# BE2022L-V10.net
KiCad netlist of a schematic drawn in Altium Designer
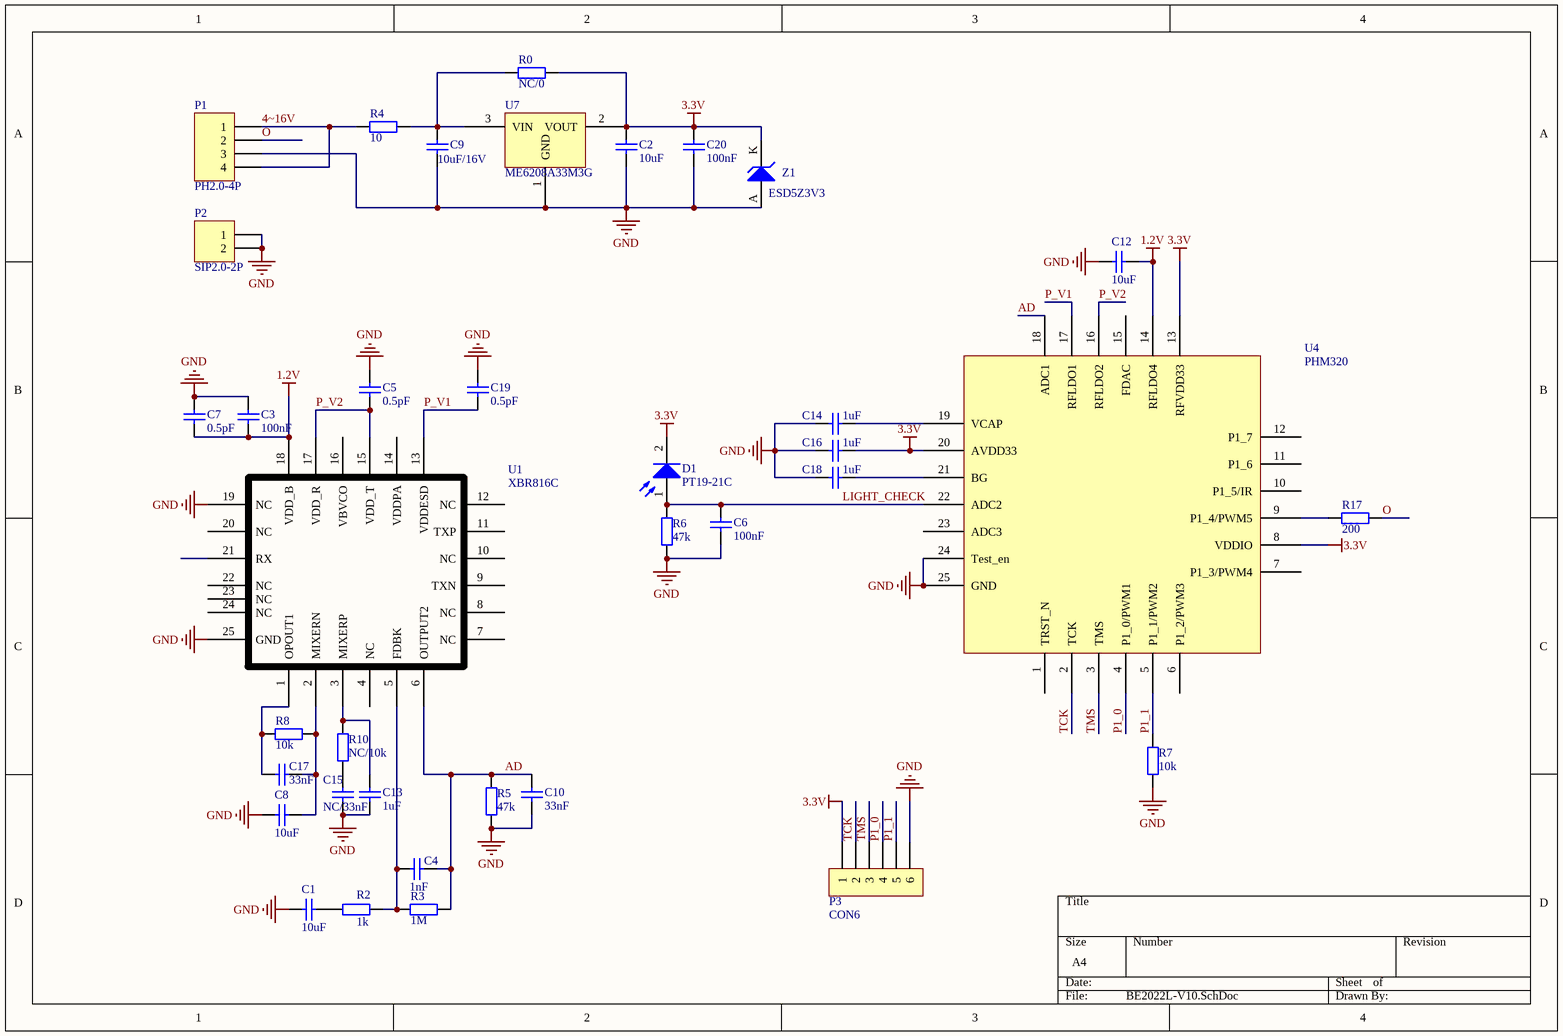
[diagram p0: BE2022L-V10.SchDoc]

(export (version "E")
  (design (tool "Eeschema 10.0.6"))
  (components
    (comp (ref "C1")
      (value "10uF")
      (footprint "C0402")
      (description "Capacitor")
      (fields (field (name "PUBLISHER") "Altium Limited"))
      (libsource (lib "") (part "Cap_1"))
    )
    (comp (ref "C2")
      (value "10uF")
      (footprint "C0402")
      (description "Capacitor")
      (fields (field (name "PUBLISHER") "Altium Limited"))
      (libsource (lib "") (part "Cap_1"))
    )
    (comp (ref "C3")
      (value "100nF")
      (footprint "C0402")
      (description "Capacitor")
      (fields (field (name "PUBLISHER") "Altium Limited"))
      (libsource (lib "") (part "Cap_1"))
    )
    (comp (ref "C4")
      (value "1nF")
      (footprint "C0402")
      (description "Capacitor")
      (fields (field (name "PUBLISHER") "Altium Limited"))
      (libsource (lib "") (part "Cap_1"))
    )
    (comp (ref "C5")
      (value "0.5pF")
      (footprint "C0402")
      (description "Capacitor")
      (fields (field (name "PUBLISHER") "Altium Limited"))
      (libsource (lib "") (part "Cap_1"))
    )
    (comp (ref "C6")
      (value "100nF")
      (footprint "C0402")
      (description "Capacitor")
      (fields (field (name "PUBLISHER") "Altium Limited"))
      (libsource (lib "") (part "Cap_1"))
    )
    (comp (ref "C7")
      (value "0.5pF")
      (footprint "C0402")
      (description "Capacitor")
      (fields (field (name "PUBLISHER") "Altium Limited"))
      (libsource (lib "") (part "Cap_1"))
    )
    (comp (ref "C8")
      (value "10uF")
      (footprint "C0402")
      (description "Capacitor")
      (fields (field (name "PUBLISHER") "Altium Limited"))
      (libsource (lib "") (part "Cap_1"))
    )
    (comp (ref "C9")
      (value "10uF/16V")
      (footprint "C0603")
      (description "Capacitor")
      (fields (field (name "PUBLISHER") "Altium Limited"))
      (libsource (lib "") (part "Cap_1"))
    )
    (comp (ref "C10")
      (value "33nF")
      (footprint "C0402")
      (description "Capacitor")
      (fields (field (name "PUBLISHER") "Altium Limited"))
      (libsource (lib "") (part "Cap_1"))
    )
    (comp (ref "C12")
      (value "10uF")
      (footprint "C0402")
      (description "Capacitor")
      (fields (field (name "PUBLISHER") "Altium Limited"))
      (libsource (lib "Miscellaneous Devices") (part "Cap"))
    )
    (comp (ref "C13")
      (value "1uF")
      (footprint "C0402")
      (description "Capacitor")
      (fields (field (name "PUBLISHER") "Altium Limited"))
      (libsource (lib "") (part "Cap_1"))
    )
    (comp (ref "C14")
      (value "1uF")
      (footprint "C0402")
      (description "Capacitor")
      (fields (field (name "PUBLISHER") "Altium Limited"))
      (libsource (lib "") (part "Cap_1"))
    )
    (comp (ref "C15")
      (value "NC/33nF")
      (footprint "C0402")
      (description "Capacitor")
      (fields (field (name "PUBLISHER") "Altium Limited"))
      (libsource (lib "") (part "Cap_1"))
    )
    (comp (ref "C16")
      (value "1uF")
      (footprint "C0402")
      (description "Capacitor")
      (fields (field (name "PUBLISHER") "Altium Limited"))
      (libsource (lib "") (part "Cap_1"))
    )
    (comp (ref "C17")
      (value "33nF")
      (footprint "C0402")
      (description "Capacitor")
      (fields (field (name "PUBLISHER") "Altium Limited"))
      (libsource (lib "") (part "Cap_1"))
    )
    (comp (ref "C18")
      (value "1uF")
      (footprint "C0402")
      (description "Capacitor")
      (fields (field (name "PUBLISHER") "Altium Limited"))
      (libsource (lib "") (part "Cap_1"))
    )
    (comp (ref "C19")
      (value "0.5pF")
      (footprint "C0402")
      (description "Capacitor")
      (fields (field (name "PUBLISHER") "Altium Limited"))
      (libsource (lib "") (part "Cap_1"))
    )
    (comp (ref "C20")
      (value "100nF")
      (footprint "C0402")
      (description "Capacitor")
      (fields (field (name "PUBLISHER") "Altium Limited"))
      (libsource (lib "") (part "Cap_1"))
    )
    (comp (ref "D1")
      (value "PT19-21C")
      (footprint "LED-0603")
      (description "Photosensitive Diode")
      (fields (field (name "PUBLISHER") "Altium Limited"))
      (libsource (lib "Miscellaneous Devices") (part "Photo Sen"))
    )
    (comp (ref "P1")
      (value "PH2.0-4P")
      (footprint "PH2.0-4P")
      (description "Header, 4-Pin")
      (fields (field (name "PUBLISHER") "Altium Limited"))
      (libsource (lib "*") (part "Header 4"))
    )
    (comp (ref "P2")
      (value "SIP2.0-2P")
      (footprint "SIP2.0-2P")
      (description "Header, 2-Pin")
      (fields (field (name "PUBLISHER") "Altium Limited"))
      (libsource (lib "Miscellaneous Connectors") (part "Header 2"))
    )
    (comp (ref "P3")
      (value "CON6")
      (footprint "CON 6PIN-1-2.0-DIP-P")
      (description "Connector")
      (libsource (lib "标准原理图库（特种板）") (part "CON6"))
    )
    (comp (ref "R0")
      (value "NC/0")
      (footprint "R0402")
      (description "Resistor")
      (fields (field (name "PUBLISHER") "Altium Limited"))
      (libsource (lib "") (part "Res2_1"))
    )
    (comp (ref "R2")
      (value "1k")
      (footprint "R0402")
      (description "Resistor")
      (fields (field (name "PUBLISHER") "Altium Limited"))
      (libsource (lib "") (part "Res2_3"))
    )
    (comp (ref "R3")
      (value "1M")
      (footprint "R0402")
      (description "Resistor")
      (fields (field (name "PUBLISHER") "Altium Limited"))
      (libsource (lib "Miscellaneous Devices") (part "Res2"))
    )
    (comp (ref "R4")
      (value "10")
      (footprint "R0402")
      (description "Resistor")
      (fields (field (name "PUBLISHER") "Altium Limited"))
      (libsource (lib "") (part "Res2_3"))
    )
    (comp (ref "R5")
      (value "47k")
      (footprint "R0402")
      (description "Resistor")
      (fields (field (name "PUBLISHER") "Altium Limited"))
      (libsource (lib "") (part "Res2_2"))
    )
    (comp (ref "R6")
      (value "47k")
      (footprint "R0402")
      (description "Resistor")
      (fields (field (name "PUBLISHER") "Altium Limited"))
      (libsource (lib "Miscellaneous Devices") (part "Res2"))
    )
    (comp (ref "R7")
      (value "10k")
      (footprint "R0402")
      (description "Resistor")
      (fields (field (name "PUBLISHER") "Altium Limited"))
      (libsource (lib "") (part "Res2_2"))
    )
    (comp (ref "R8")
      (value "10k")
      (footprint "R0402")
      (description "Resistor")
      (fields (field (name "PUBLISHER") "Altium Limited"))
      (libsource (lib "Miscellaneous Devices") (part "Res2"))
    )
    (comp (ref "R10")
      (value "NC/10k")
      (footprint "R0402")
      (description "Resistor")
      (fields (field (name "PUBLISHER") "Altium Limited"))
      (libsource (lib "") (part "Res2_2"))
    )
    (comp (ref "R17")
      (value "200")
      (footprint "R0402")
      (description "Resistor")
      (fields (field (name "PUBLISHER") "Altium Limited"))
      (libsource (lib "") (part "Res2_1"))
    )
    (comp (ref "U1")
      (value "XBR816C")
      (footprint "QFN24-1")
      (libsource (lib "Schlib1") (part "XBR1000_24_1"))
    )
    (comp (ref "U4") (value "PHM320") (footprint "QFN24") (libsource (lib "ZWZ") (part "PHM320")))
    (comp (ref "U7")
      (value "ME6208A33M3G")
      (footprint "SOT-23-L")
      (libsource (lib "Schlib1") (part "SSP6206"))
    )
    (comp (ref "Z1")
      (value "ESD5Z3V3")
      (footprint "SOD-523")
      (description "Zener Diode")
      (fields (field (name "PUBLISHER") "Altium Limited"))
      (libsource (lib "Miscellaneous Devices") (part "D Zener"))
    )
  )
  (nets
    (net (code "1") (name "/4~16V") (class "Default")
      (node (ref "P1") (pin "1") (pinfunction "1_1") (pintype "passive"))
      (node (ref "P1") (pin "4") (pinfunction "4_4") (pintype "passive"))
      (node (ref "R4") (pin "1") (pinfunction "1_1") (pintype "passive"))
    )
    (net (code "2") (name "/AD") (class "Default")
      (node (ref "C10") (pin "1") (pinfunction "1_1") (pintype "passive"))
      (node (ref "C4") (pin "1") (pinfunction "1_1") (pintype "passive"))
      (node (ref "R3") (pin "1") (pinfunction "1_1") (pintype "passive"))
      (node (ref "R5") (pin "1") (pinfunction "1_1") (pintype "passive"))
      (node (ref "U1") (pin "6") (pinfunction "OUTPUT2_6") (pintype "passive"))
      (node (ref "U4") (pin "18") (pinfunction "ADC1_18") (pintype "passive"))
    )
    (net (code "3") (name "/LIGHT_CHECK") (class "Default")
      (node (ref "C6") (pin "1") (pinfunction "1_1") (pintype "passive"))
      (node (ref "D1") (pin "1") (pinfunction "A_1") (pintype "passive"))
      (node (ref "R6") (pin "1") (pinfunction "1_1") (pintype "passive"))
      (node (ref "U4") (pin "22") (pinfunction "ADC2_22") (pintype "passive"))
    )
    (net (code "4") (name "/O") (class "Default")
      (node (ref "P1") (pin "2") (pinfunction "2_2") (pintype "passive"))
      (node (ref "R17") (pin "2") (pinfunction "2_2") (pintype "passive"))
    )
    (net (code "5") (name "/P1_0") (class "Default")
      (node (ref "P3") (pin "4") (pinfunction "4_4") (pintype "passive"))
      (node (ref "U4") (pin "4") (pinfunction "P1_0/PWM1_4") (pintype "passive"))
    )
    (net (code "6") (name "/P1_1") (class "Default")
      (node (ref "P3") (pin "5") (pinfunction "5_5") (pintype "passive"))
      (node (ref "R7") (pin "1") (pinfunction "1_1") (pintype "passive"))
      (node (ref "U4") (pin "5") (pinfunction "P1_1/PWM2_5") (pintype "passive"))
    )
    (net (code "7") (name "/P_V1") (class "Default")
      (node (ref "C19") (pin "1") (pinfunction "1_1") (pintype "passive"))
      (node (ref "U1") (pin "13") (pinfunction "VDDESD_13") (pintype "passive"))
      (node (ref "U4") (pin "17") (pinfunction "RFLDO1_17") (pintype "passive"))
    )
    (net (code "8") (name "/P_V2") (class "Default")
      (node (ref "C5") (pin "1") (pinfunction "1_1") (pintype "passive"))
      (node (ref "U1") (pin "15") (pinfunction "VDD_T_15") (pintype "passive"))
      (node (ref "U1") (pin "17") (pinfunction "VDD_R_17") (pintype "passive"))
      (node (ref "U4") (pin "16") (pinfunction "RFLDO2_16") (pintype "passive"))
    )
    (net (code "9") (name "/TCK") (class "Default")
      (node (ref "P3") (pin "2") (pinfunction "2_2") (pintype "passive"))
      (node (ref "U4") (pin "2") (pinfunction "TCK_2") (pintype "passive"))
    )
    (net (code "10") (name "/TMS") (class "Default")
      (node (ref "P3") (pin "3") (pinfunction "3_3") (pintype "passive"))
      (node (ref "U4") (pin "3") (pinfunction "TMS_3") (pintype "passive"))
    )
    (net (code "11") (name "1.2V") (class "Default")
      (node (ref "C12") (pin "1") (pinfunction "1_1") (pintype "passive"))
      (node (ref "C3") (pin "2") (pinfunction "2_2") (pintype "passive"))
      (node (ref "C7") (pin "1") (pinfunction "1_1") (pintype "passive"))
      (node (ref "U1") (pin "18") (pinfunction "VDD_B_18") (pintype "passive"))
      (node (ref "U4") (pin "14") (pinfunction "RFLDO4_14") (pintype "passive"))
    )
    (net (code "12") (name "3.3V") (class "Default")
      (node (ref "C16") (pin "1") (pinfunction "1_1") (pintype "passive"))
      (node (ref "C2") (pin "1") (pinfunction "1_1") (pintype "passive"))
      (node (ref "C20") (pin "2") (pinfunction "2_2") (pintype "passive"))
      (node (ref "D1") (pin "2") (pinfunction "K_2") (pintype "passive"))
      (node (ref "P3") (pin "1") (pinfunction "1_1") (pintype "passive"))
      (node (ref "R0") (pin "2") (pinfunction "2_2") (pintype "passive"))
      (node (ref "U4") (pin "13") (pinfunction "RFVDD33_13") (pintype "passive"))
      (node (ref "U4") (pin "20") (pinfunction "AVDD33_20") (pintype "passive"))
      (node (ref "U4") (pin "8") (pinfunction "VDDIO_8") (pintype "passive"))
      (node (ref "U7") (pin "2") (pinfunction "VOUT_2") (pintype "passive"))
      (node (ref "Z1") (pin "K") (pinfunction "K_K") (pintype "passive"))
    )
    (net (code "13") (name "GND") (class "Default")
      (node (ref "C1") (pin "2") (pinfunction "2_2") (pintype "passive"))
      (node (ref "C10") (pin "2") (pinfunction "2_2") (pintype "passive"))
      (node (ref "C12") (pin "2") (pinfunction "2_2") (pintype "passive"))
      (node (ref "C13") (pin "1") (pinfunction "1_1") (pintype "passive"))
      (node (ref "C14") (pin "2") (pinfunction "2_2") (pintype "passive"))
      (node (ref "C15") (pin "1") (pinfunction "1_1") (pintype "passive"))
      (node (ref "C16") (pin "2") (pinfunction "2_2") (pintype "passive"))
      (node (ref "C18") (pin "2") (pinfunction "2_2") (pintype "passive"))
      (node (ref "C19") (pin "2") (pinfunction "2_2") (pintype "passive"))
      (node (ref "C2") (pin "2") (pinfunction "2_2") (pintype "passive"))
      (node (ref "C20") (pin "1") (pinfunction "1_1") (pintype "passive"))
      (node (ref "C3") (pin "1") (pinfunction "1_1") (pintype "passive"))
      (node (ref "C5") (pin "2") (pinfunction "2_2") (pintype "passive"))
      (node (ref "C6") (pin "2") (pinfunction "2_2") (pintype "passive"))
      (node (ref "C7") (pin "2") (pinfunction "2_2") (pintype "passive"))
      (node (ref "C8") (pin "1") (pinfunction "1_1") (pintype "passive"))
      (node (ref "C9") (pin "2") (pinfunction "2_2") (pintype "passive"))
      (node (ref "P1") (pin "3") (pinfunction "3_3") (pintype "passive"))
      (node (ref "P2") (pin "1") (pinfunction "1_1") (pintype "passive"))
      (node (ref "P2") (pin "2") (pinfunction "2_2") (pintype "passive"))
      (node (ref "P3") (pin "6") (pinfunction "6_6") (pintype "passive"))
      (node (ref "R5") (pin "2") (pinfunction "2_2") (pintype "passive"))
      (node (ref "R6") (pin "2") (pinfunction "2_2") (pintype "passive"))
      (node (ref "R7") (pin "2") (pinfunction "2_2") (pintype "passive"))
      (node (ref "U1") (pin "19") (pinfunction "NC_19") (pintype "passive"))
      (node (ref "U1") (pin "25") (pinfunction "GND_25") (pintype "passive"))
      (node (ref "U4") (pin "24") (pinfunction "Test_en_24") (pintype "passive"))
      (node (ref "U4") (pin "25") (pinfunction "GND_25") (pintype "passive"))
      (node (ref "U7") (pin "1") (pinfunction "GND_1") (pintype "passive"))
      (node (ref "Z1") (pin "A") (pinfunction "A_A") (pintype "passive"))
    )
    (net (code "14") (name "Net-(C1-Pad1)") (class "Default")
      (node (ref "C1") (pin "1") (pinfunction "1_1") (pintype "passive"))
      (node (ref "R2") (pin "1") (pinfunction "1_1") (pintype "passive"))
    )
    (net (code "15") (name "Net-(C15-Pad2)") (class "Default")
      (node (ref "C15") (pin "2") (pinfunction "2_2") (pintype "passive"))
      (node (ref "R10") (pin "2") (pinfunction "2_2") (pintype "passive"))
    )
    (net (code "16") (name "Net-(U1-FDBK)") (class "Default")
      (node (ref "C4") (pin "2") (pinfunction "2_2") (pintype "passive"))
      (node (ref "R2") (pin "2") (pinfunction "2_2") (pintype "passive"))
      (node (ref "R3") (pin "2") (pinfunction "2_2") (pintype "passive"))
      (node (ref "U1") (pin "5") (pinfunction "FDBK_5") (pintype "passive"))
    )
    (net (code "17") (name "Net-(U1-MIXERN)") (class "Default")
      (node (ref "C17") (pin "1") (pinfunction "1_1") (pintype "passive"))
      (node (ref "C8") (pin "2") (pinfunction "2_2") (pintype "passive"))
      (node (ref "R8") (pin "1") (pinfunction "1_1") (pintype "passive"))
      (node (ref "U1") (pin "2") (pinfunction "MIXERN_2") (pintype "passive"))
    )
    (net (code "18") (name "Net-(U1-MIXERP)") (class "Default")
      (node (ref "C13") (pin "2") (pinfunction "2_2") (pintype "passive"))
      (node (ref "R10") (pin "1") (pinfunction "1_1") (pintype "passive"))
      (node (ref "U1") (pin "3") (pinfunction "MIXERP_3") (pintype "passive"))
    )
    (net (code "19") (name "Net-(U1-OPOUT1)") (class "Default")
      (node (ref "C17") (pin "2") (pinfunction "2_2") (pintype "passive"))
      (node (ref "R8") (pin "2") (pinfunction "2_2") (pintype "passive"))
      (node (ref "U1") (pin "1") (pinfunction "OPOUT1_1") (pintype "passive"))
    )
    (net (code "20") (name "Net-(U4-BG)") (class "Default")
      (node (ref "C18") (pin "1") (pinfunction "1_1") (pintype "passive"))
      (node (ref "U4") (pin "21") (pinfunction "BG_21") (pintype "passive"))
    )
    (net (code "21") (name "Net-(U4-P1_4{slash}PWM5)") (class "Default")
      (node (ref "R17") (pin "1") (pinfunction "1_1") (pintype "passive"))
      (node (ref "U4") (pin "9") (pinfunction "P1_4/PWM5_9") (pintype "passive"))
    )
    (net (code "22") (name "Net-(U4-VCAP)") (class "Default")
      (node (ref "C14") (pin "1") (pinfunction "1_1") (pintype "passive"))
      (node (ref "U4") (pin "19") (pinfunction "VCAP_19") (pintype "passive"))
    )
    (net (code "23") (name "Net-(U7-VIN)") (class "Default")
      (node (ref "C9") (pin "1") (pinfunction "1_1") (pintype "passive"))
      (node (ref "R0") (pin "1") (pinfunction "1_1") (pintype "passive"))
      (node (ref "R4") (pin "2") (pinfunction "2_2") (pintype "passive"))
      (node (ref "U7") (pin "3") (pinfunction "VIN_3") (pintype "passive"))
    )
    (net (code "24") (name "unconnected-(U1-NC-Pad4)") (class "Default")
      (node (ref "U1") (pin "4") (pinfunction "NC_4") (pintype "passive"))
    )
    (net (code "25") (name "unconnected-(U1-NC-Pad7)") (class "Default")
      (node (ref "U1") (pin "7") (pinfunction "NC_7") (pintype "passive"))
    )
    (net (code "26") (name "unconnected-(U1-NC-Pad8)") (class "Default")
      (node (ref "U1") (pin "8") (pinfunction "NC_8") (pintype "passive"))
    )
    (net (code "27") (name "unconnected-(U1-NC-Pad10)") (class "Default")
      (node (ref "U1") (pin "10") (pinfunction "NC_10") (pintype "passive"))
    )
    (net (code "28") (name "unconnected-(U1-NC-Pad12)") (class "Default")
      (node (ref "U1") (pin "12") (pinfunction "NC_12") (pintype "passive"))
    )
    (net (code "29") (name "unconnected-(U1-NC-Pad20)") (class "Default")
      (node (ref "U1") (pin "20") (pinfunction "NC_20") (pintype "passive"))
    )
    (net (code "30") (name "unconnected-(U1-NC-Pad22)") (class "Default")
      (node (ref "U1") (pin "22") (pinfunction "NC_22") (pintype "passive"))
    )
    (net (code "31") (name "unconnected-(U1-NC-Pad23)") (class "Default")
      (node (ref "U1") (pin "23") (pinfunction "NC_23") (pintype "passive"))
    )
    (net (code "32") (name "unconnected-(U1-NC-Pad24)") (class "Default")
      (node (ref "U1") (pin "24") (pinfunction "NC_24") (pintype "passive"))
    )
    (net (code "33") (name "unconnected-(U1-RX-Pad21)") (class "Default")
      (node (ref "U1") (pin "21") (pinfunction "RX_21") (pintype "passive"))
    )
    (net (code "34") (name "unconnected-(U1-TXN-Pad9)") (class "Default")
      (node (ref "U1") (pin "9") (pinfunction "TXN_9") (pintype "passive"))
    )
    (net (code "35") (name "unconnected-(U1-TXP-Pad11)") (class "Default")
      (node (ref "U1") (pin "11") (pinfunction "TXP_11") (pintype "passive"))
    )
    (net (code "36") (name "unconnected-(U1-VBVCO-Pad16)") (class "Default")
      (node (ref "U1") (pin "16") (pinfunction "VBVCO_16") (pintype "passive"))
    )
    (net (code "37") (name "unconnected-(U1-VDDPA-Pad14)") (class "Default")
      (node (ref "U1") (pin "14") (pinfunction "VDDPA_14") (pintype "passive"))
    )
    (net (code "38") (name "unconnected-(U4-ADC3-Pad23)") (class "Default")
      (node (ref "U4") (pin "23") (pinfunction "ADC3_23") (pintype "passive"))
    )
    (net (code "39") (name "unconnected-(U4-FDAC-Pad15)") (class "Default")
      (node (ref "U4") (pin "15") (pinfunction "FDAC_15") (pintype "passive"))
    )
    (net (code "40") (name "unconnected-(U4-P1_2{slash}PWM3-Pad6)") (class "Default")
      (node (ref "U4") (pin "6") (pinfunction "P1_2/PWM3_6") (pintype "passive"))
    )
    (net (code "41") (name "unconnected-(U4-P1_3{slash}PWM4-Pad7)") (class "Default")
      (node (ref "U4") (pin "7") (pinfunction "P1_3/PWM4_7") (pintype "passive"))
    )
    (net (code "42") (name "unconnected-(U4-P1_5{slash}IR-Pad10)") (class "Default")
      (node (ref "U4") (pin "10") (pinfunction "P1_5/IR_10") (pintype "passive"))
    )
    (net (code "43") (name "unconnected-(U4-P1_6-Pad11)") (class "Default")
      (node (ref "U4") (pin "11") (pinfunction "P1_6_11") (pintype "passive"))
    )
    (net (code "44") (name "unconnected-(U4-P1_7-Pad12)") (class "Default")
      (node (ref "U4") (pin "12") (pinfunction "P1_7_12") (pintype "passive"))
    )
    (net (code "45") (name "unconnected-(U4-TRST_N-Pad1)") (class "Default")
      (node (ref "U4") (pin "1") (pinfunction "TRST_N_1") (pintype "passive"))
    )
  )
)
